# servo_board.net
KiCad netlist of a schematic drawn in EAGLE
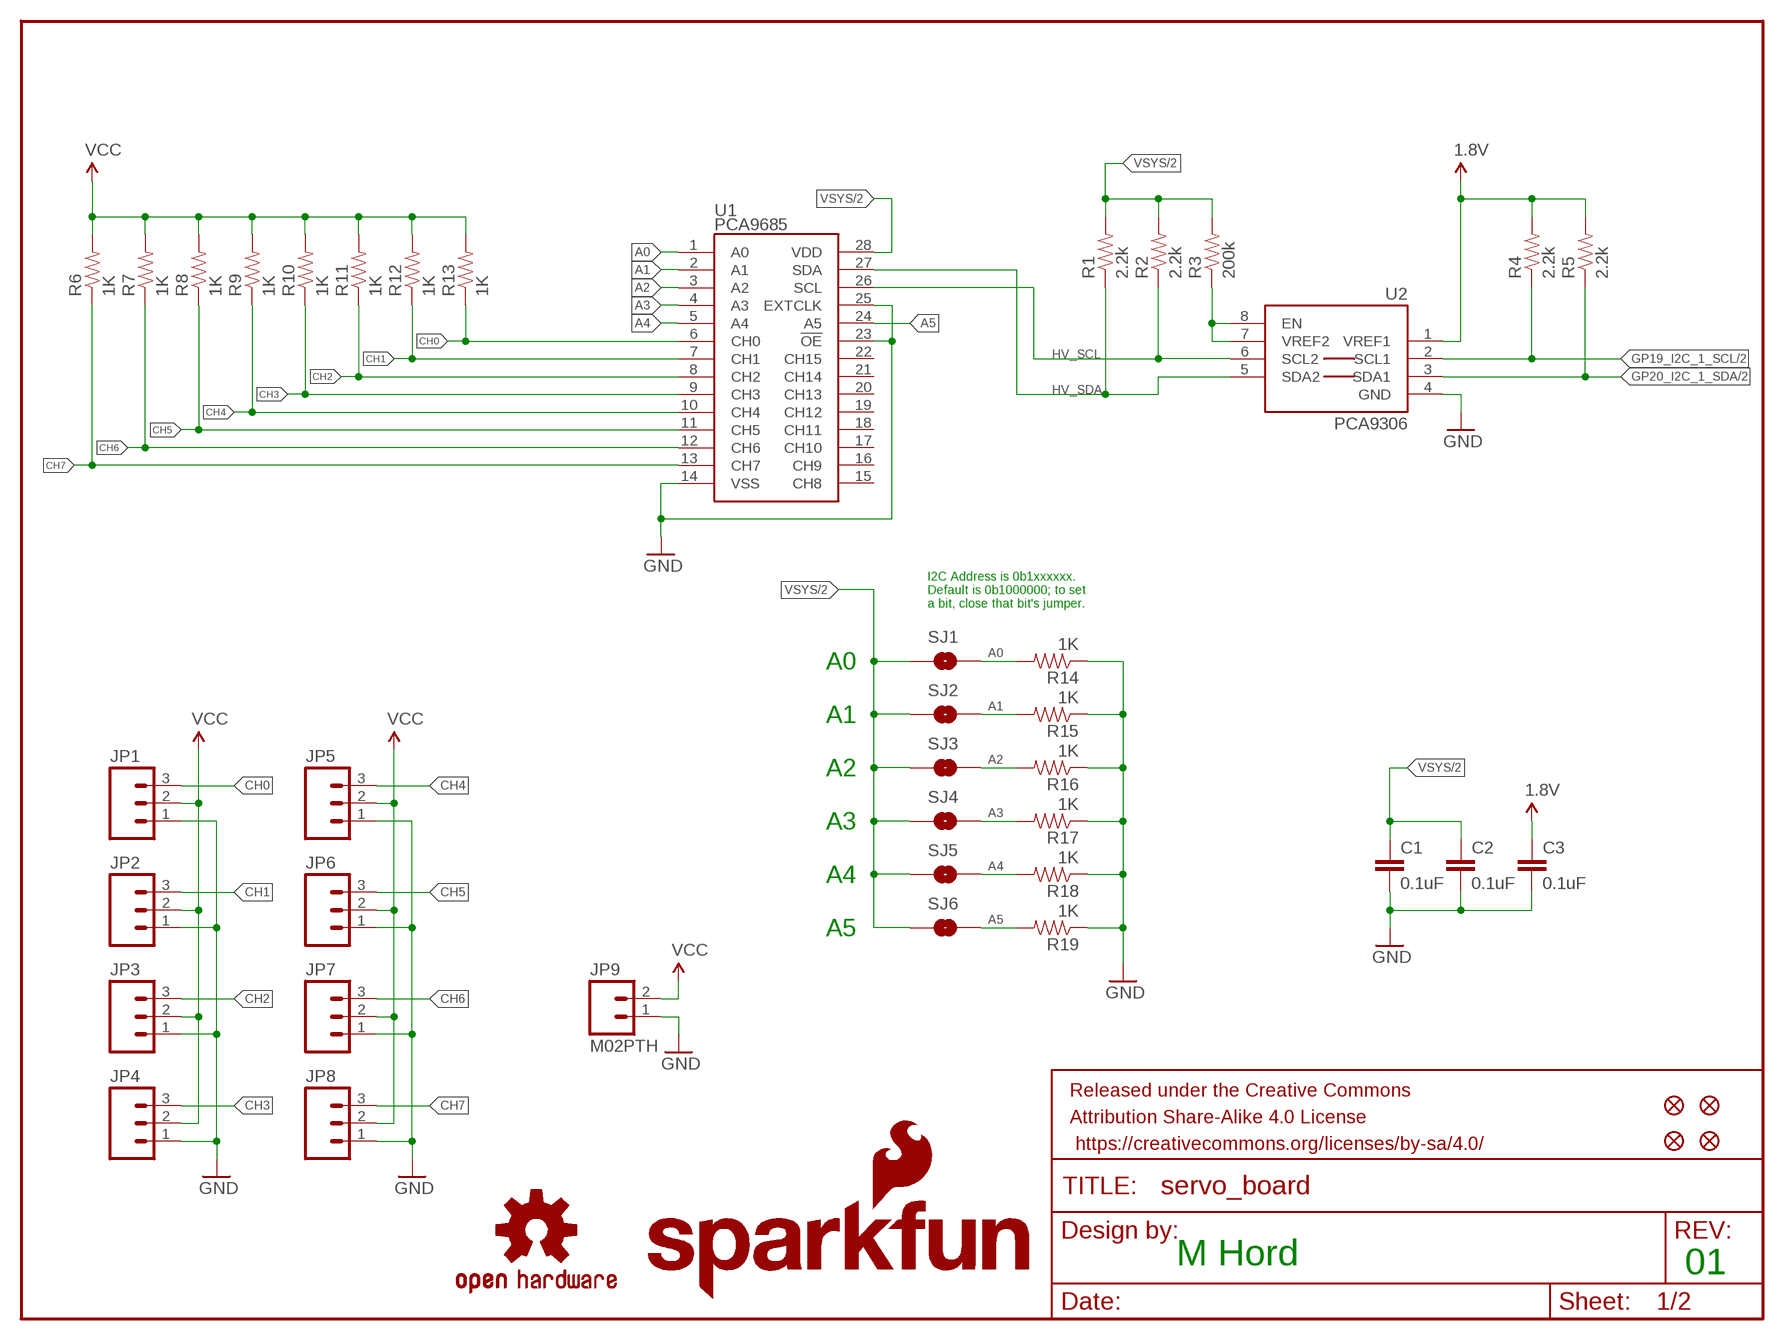
[diagram p0: schematic, sheet 1]
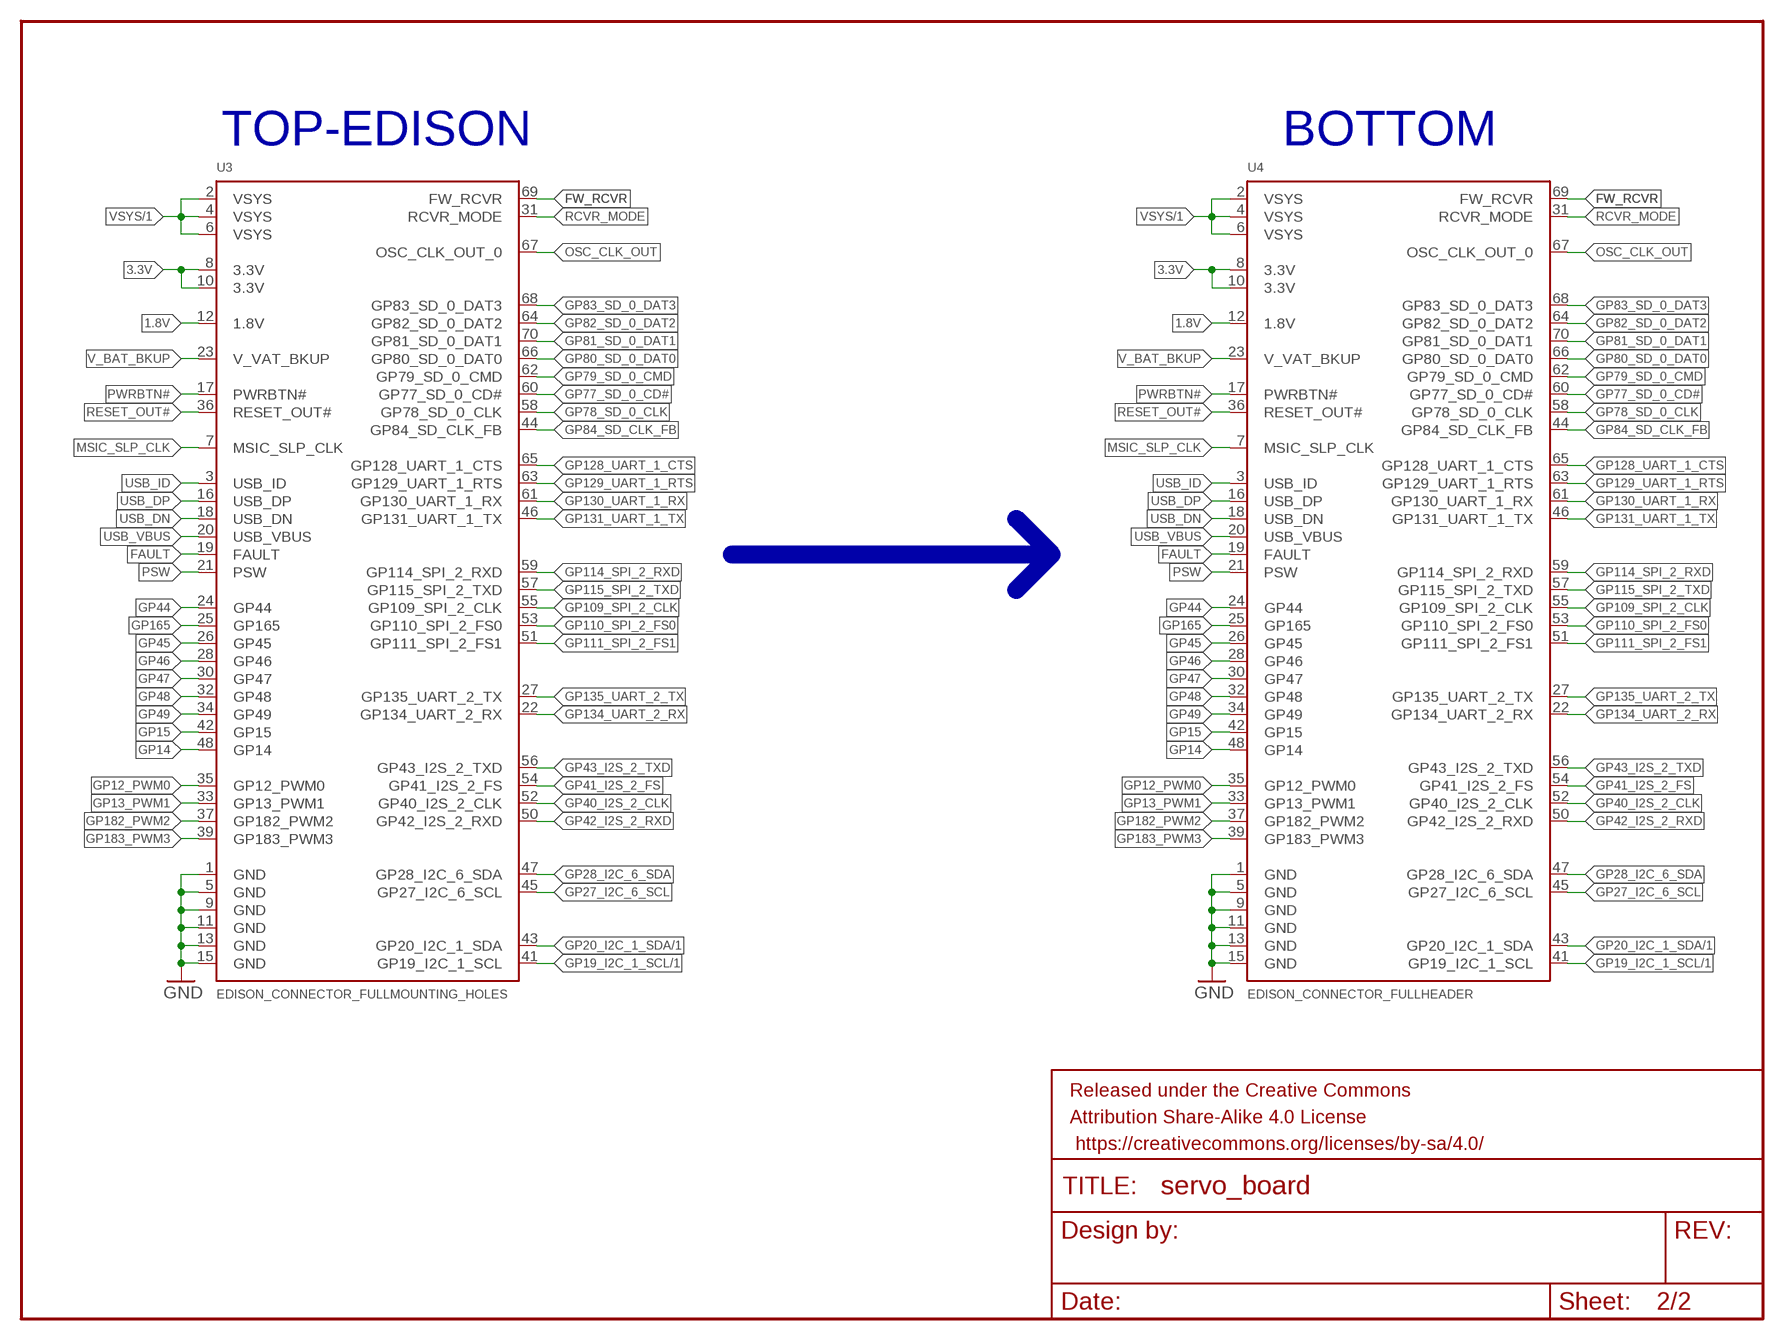
[diagram p1: schematic, sheet 2]

(export (version "E")
  (design (tool "Eeschema 10.0.6"))
  (components
    (comp (ref "FRAME2")
      (value "FRAME-LETTER")
      (footprint "eagle-import:CREATIVE_COMMONS")
      (libsource (lib "eagle-import") (part "FRAME-LETTER"))
    )
    (comp (ref "U3")
      (value "EDISON_CONNECTOR_FULLMOUNTING_HOLES")
      (footprint "eagle-import:EDISON_DAUGHTER")
      (libsource (lib "eagle-import") (part "EDISON_CONNECTOR_FULLMOUNTING_HOLES"))
    )
    (comp (ref "U4")
      (value "EDISON_CONNECTOR_FULLHEADER")
      (footprint "eagle-import:DF40C-70DP-0.4(51)")
      (libsource (lib "eagle-import") (part "EDISON_CONNECTOR_FULLHEADER"))
    )
    (comp (ref "C1")
      (value "0.1uF")
      (footprint "eagle-import:0603-CAP")
      (libsource (lib "eagle-import") (part "0.1UF-25V(+80/-20%)(0603)"))
    )
    (comp (ref "C2")
      (value "0.1uF")
      (footprint "eagle-import:0603-CAP")
      (libsource (lib "eagle-import") (part "0.1UF-25V(+80/-20%)(0603)"))
    )
    (comp (ref "C3")
      (value "0.1uF")
      (footprint "eagle-import:0603-CAP")
      (libsource (lib "eagle-import") (part "0.1UF-25V(+80/-20%)(0603)"))
    )
    (comp (ref "FID1")
      (value "FIDUCIAL1X2")
      (footprint "eagle-import:FIDUCIAL-1X2")
      (libsource (lib "eagle-import") (part "FIDUCIAL1X2"))
    )
    (comp (ref "FID2")
      (value "FIDUCIAL1X2")
      (footprint "eagle-import:FIDUCIAL-1X2")
      (libsource (lib "eagle-import") (part "FIDUCIAL1X2"))
    )
    (comp (ref "FID3")
      (value "FIDUCIAL1X2")
      (footprint "eagle-import:FIDUCIAL-1X2")
      (libsource (lib "eagle-import") (part "FIDUCIAL1X2"))
    )
    (comp (ref "FID4")
      (value "FIDUCIAL1X2")
      (footprint "eagle-import:FIDUCIAL-1X2")
      (libsource (lib "eagle-import") (part "FIDUCIAL1X2"))
    )
    (comp (ref "FRAME1")
      (value "FRAME-LETTER")
      (footprint "eagle-import:CREATIVE_COMMONS")
      (libsource (lib "eagle-import") (part "FRAME-LETTER"))
    )
    (comp (ref "JP1")
      (value "M03PTH")
      (footprint "eagle-import:1X03")
      (libsource (lib "eagle-import") (part "M03PTH"))
    )
    (comp (ref "JP2")
      (value "M03PTH")
      (footprint "eagle-import:1X03")
      (libsource (lib "eagle-import") (part "M03PTH"))
    )
    (comp (ref "JP3")
      (value "M03PTH")
      (footprint "eagle-import:1X03")
      (libsource (lib "eagle-import") (part "M03PTH"))
    )
    (comp (ref "JP4")
      (value "M03PTH")
      (footprint "eagle-import:1X03")
      (libsource (lib "eagle-import") (part "M03PTH"))
    )
    (comp (ref "JP5")
      (value "M03PTH")
      (footprint "eagle-import:1X03")
      (libsource (lib "eagle-import") (part "M03PTH"))
    )
    (comp (ref "JP6")
      (value "M03PTH")
      (footprint "eagle-import:1X03")
      (libsource (lib "eagle-import") (part "M03PTH"))
    )
    (comp (ref "JP7")
      (value "M03PTH")
      (footprint "eagle-import:1X03")
      (libsource (lib "eagle-import") (part "M03PTH"))
    )
    (comp (ref "JP8")
      (value "M03PTH")
      (footprint "eagle-import:1X03")
      (libsource (lib "eagle-import") (part "M03PTH"))
    )
    (comp (ref "JP9")
      (value "M02PTH")
      (footprint "eagle-import:1X02")
      (libsource (lib "eagle-import") (part "M02PTH"))
    )
    (comp (ref "LOGO1")
      (value "SFE_LOGO_NAME_FLAME.1_INCH")
      (footprint "eagle-import:SFE_LOGO_NAME_FLAME_.1")
      (libsource (lib "eagle-import") (part "SFE_LOGO_NAME_FLAME.1_INCH"))
    )
    (comp (ref "LOGO2")
      (value "OSHW-LOGOS")
      (footprint "eagle-import:OSHW-LOGO-S")
      (libsource (lib "eagle-import") (part "OSHW-LOGOS"))
    )
    (comp (ref "LOGO3")
      (value "SFE_LOGO_NAME_FLAME.1_INCH")
      (footprint "eagle-import:SFE_LOGO_NAME_FLAME_.1")
      (libsource (lib "eagle-import") (part "SFE_LOGO_NAME_FLAME.1_INCH"))
    )
    (comp (ref "LOGO4")
      (value "OSHW-LOGOS")
      (footprint "eagle-import:OSHW-LOGO-S")
      (libsource (lib "eagle-import") (part "OSHW-LOGOS"))
    )
    (comp (ref "R1")
      (value "2.2k")
      (footprint "eagle-import:0603-RES")
      (libsource (lib "eagle-import") (part "2.2KOHM1/10W1%(0603)"))
    )
    (comp (ref "R2")
      (value "2.2k")
      (footprint "eagle-import:0603-RES")
      (libsource (lib "eagle-import") (part "2.2KOHM1/10W1%(0603)"))
    )
    (comp (ref "R3")
      (value "200k")
      (footprint "eagle-import:0603-RES")
      (libsource (lib "eagle-import") (part "200KOHM1/10W1%(0603)200K"))
    )
    (comp (ref "R4")
      (value "2.2k")
      (footprint "eagle-import:0603-RES")
      (libsource (lib "eagle-import") (part "2.2KOHM1/10W1%(0603)"))
    )
    (comp (ref "R5")
      (value "2.2k")
      (footprint "eagle-import:0603-RES")
      (libsource (lib "eagle-import") (part "2.2KOHM1/10W1%(0603)"))
    )
    (comp (ref "R6")
      (value "1K")
      (footprint "eagle-import:0603-RES")
      (libsource (lib "eagle-import") (part "1KOHM1/10W1%(0603)"))
    )
    (comp (ref "R7")
      (value "1K")
      (footprint "eagle-import:0603-RES")
      (libsource (lib "eagle-import") (part "1KOHM1/10W1%(0603)"))
    )
    (comp (ref "R8")
      (value "1K")
      (footprint "eagle-import:0603-RES")
      (libsource (lib "eagle-import") (part "1KOHM1/10W1%(0603)"))
    )
    (comp (ref "R9")
      (value "1K")
      (footprint "eagle-import:0603-RES")
      (libsource (lib "eagle-import") (part "1KOHM1/10W1%(0603)"))
    )
    (comp (ref "R10")
      (value "1K")
      (footprint "eagle-import:0603-RES")
      (libsource (lib "eagle-import") (part "1KOHM1/10W1%(0603)"))
    )
    (comp (ref "R11")
      (value "1K")
      (footprint "eagle-import:0603-RES")
      (libsource (lib "eagle-import") (part "1KOHM1/10W1%(0603)"))
    )
    (comp (ref "R12")
      (value "1K")
      (footprint "eagle-import:0603-RES")
      (libsource (lib "eagle-import") (part "1KOHM1/10W1%(0603)"))
    )
    (comp (ref "R13")
      (value "1K")
      (footprint "eagle-import:0603-RES")
      (libsource (lib "eagle-import") (part "1KOHM1/10W1%(0603)"))
    )
    (comp (ref "R14")
      (value "1K")
      (footprint "eagle-import:0603-RES")
      (libsource (lib "eagle-import") (part "1KOHM1/10W1%(0603)"))
    )
    (comp (ref "R15")
      (value "1K")
      (footprint "eagle-import:0603-RES")
      (libsource (lib "eagle-import") (part "1KOHM1/10W1%(0603)"))
    )
    (comp (ref "R16")
      (value "1K")
      (footprint "eagle-import:0603-RES")
      (libsource (lib "eagle-import") (part "1KOHM1/10W1%(0603)"))
    )
    (comp (ref "R17")
      (value "1K")
      (footprint "eagle-import:0603-RES")
      (libsource (lib "eagle-import") (part "1KOHM1/10W1%(0603)"))
    )
    (comp (ref "R18")
      (value "1K")
      (footprint "eagle-import:0603-RES")
      (libsource (lib "eagle-import") (part "1KOHM1/10W1%(0603)"))
    )
    (comp (ref "R19")
      (value "1K")
      (footprint "eagle-import:0603-RES")
      (libsource (lib "eagle-import") (part "1KOHM1/10W1%(0603)"))
    )
    (comp (ref "SJ1")
      (value "JUMPER-PAD-2-NOYES_SILK")
      (footprint "eagle-import:PAD-JUMPER-2-NO_YES_SILK")
      (libsource (lib "eagle-import") (part "JUMPER-PAD-2-NOYES_SILK"))
    )
    (comp (ref "SJ2")
      (value "JUMPER-PAD-2-NOYES_SILK")
      (footprint "eagle-import:PAD-JUMPER-2-NO_YES_SILK")
      (libsource (lib "eagle-import") (part "JUMPER-PAD-2-NOYES_SILK"))
    )
    (comp (ref "SJ3")
      (value "JUMPER-PAD-2-NOYES_SILK")
      (footprint "eagle-import:PAD-JUMPER-2-NO_YES_SILK")
      (libsource (lib "eagle-import") (part "JUMPER-PAD-2-NOYES_SILK"))
    )
    (comp (ref "SJ4")
      (value "JUMPER-PAD-2-NOYES_SILK")
      (footprint "eagle-import:PAD-JUMPER-2-NO_YES_SILK")
      (libsource (lib "eagle-import") (part "JUMPER-PAD-2-NOYES_SILK"))
    )
    (comp (ref "SJ5")
      (value "JUMPER-PAD-2-NOYES_SILK")
      (footprint "eagle-import:PAD-JUMPER-2-NO_YES_SILK")
      (libsource (lib "eagle-import") (part "JUMPER-PAD-2-NOYES_SILK"))
    )
    (comp (ref "SJ6")
      (value "JUMPER-PAD-2-NOYES_SILK")
      (footprint "eagle-import:PAD-JUMPER-2-NO_YES_SILK")
      (libsource (lib "eagle-import") (part "JUMPER-PAD-2-NOYES_SILK"))
    )
    (comp (ref "U1")
      (value "PCA9685")
      (footprint "eagle-import:TSSOP-28_4MM")
      (libsource (lib "eagle-import") (part "PCA9685"))
    )
    (comp (ref "U2")
      (value "PCA9306")
      (footprint "eagle-import:PCA9306DC-1_1")
      (libsource (lib "eagle-import") (part "PCA9306PCA9306DC-1{colon}1"))
    )
  )
  (nets
    (net (code "1") (name "1.8V") (class "Default")
      (node (ref "C3") (pin "1") (pinfunction "1_1") (pintype "passive"))
      (node (ref "R4") (pin "2") (pinfunction "2_2") (pintype "passive"))
      (node (ref "R5") (pin "2") (pinfunction "2_2") (pintype "passive"))
      (node (ref "U2") (pin "1") (pinfunction "VREF1_1") (pintype "bidirectional"))
      (node (ref "U3") (pin "12") (pinfunction "1.8V_12") (pintype "bidirectional"))
      (node (ref "U4") (pin "12") (pinfunction "1.8V_12") (pintype "bidirectional"))
    )
    (net (code "2") (name "3.3V") (class "Default")
      (node (ref "U3") (pin "10") (pinfunction "3.3V_10") (pintype "bidirectional"))
      (node (ref "U3") (pin "8") (pinfunction "3.3V_8") (pintype "bidirectional"))
      (node (ref "U4") (pin "10") (pinfunction "3.3V_10") (pintype "bidirectional"))
      (node (ref "U4") (pin "8") (pinfunction "3.3V_8") (pintype "bidirectional"))
    )
    (net (code "3") (name "A0") (class "Default")
      (node (ref "R14") (pin "2") (pinfunction "2_2") (pintype "passive"))
      (node (ref "SJ1") (pin "2") (pinfunction "2_2") (pintype "passive"))
      (node (ref "U1") (pin "1") (pinfunction "A0_1") (pintype "bidirectional"))
    )
    (net (code "4") (name "A1") (class "Default")
      (node (ref "R15") (pin "2") (pinfunction "2_2") (pintype "passive"))
      (node (ref "SJ2") (pin "2") (pinfunction "2_2") (pintype "passive"))
      (node (ref "U1") (pin "2") (pinfunction "A1_2") (pintype "bidirectional"))
    )
    (net (code "5") (name "A2") (class "Default")
      (node (ref "R16") (pin "2") (pinfunction "2_2") (pintype "passive"))
      (node (ref "SJ3") (pin "2") (pinfunction "2_2") (pintype "passive"))
      (node (ref "U1") (pin "3") (pinfunction "A2_3") (pintype "bidirectional"))
    )
    (net (code "6") (name "A3") (class "Default")
      (node (ref "R17") (pin "2") (pinfunction "2_2") (pintype "passive"))
      (node (ref "SJ4") (pin "2") (pinfunction "2_2") (pintype "passive"))
      (node (ref "U1") (pin "4") (pinfunction "A3_4") (pintype "bidirectional"))
    )
    (net (code "7") (name "A4") (class "Default")
      (node (ref "R18") (pin "2") (pinfunction "2_2") (pintype "passive"))
      (node (ref "SJ5") (pin "2") (pinfunction "2_2") (pintype "passive"))
      (node (ref "U1") (pin "5") (pinfunction "A4_5") (pintype "bidirectional"))
    )
    (net (code "8") (name "A5") (class "Default")
      (node (ref "R19") (pin "2") (pinfunction "2_2") (pintype "passive"))
      (node (ref "SJ6") (pin "2") (pinfunction "2_2") (pintype "passive"))
      (node (ref "U1") (pin "24") (pinfunction "A5_24") (pintype "bidirectional"))
    )
    (net (code "9") (name "CH0") (class "Default")
      (node (ref "JP1") (pin "3") (pinfunction "3_3") (pintype "passive"))
      (node (ref "R13") (pin "1") (pinfunction "1_1") (pintype "passive"))
      (node (ref "U1") (pin "6") (pinfunction "CH0_6") (pintype "bidirectional"))
    )
    (net (code "10") (name "CH1") (class "Default")
      (node (ref "JP2") (pin "3") (pinfunction "3_3") (pintype "passive"))
      (node (ref "R12") (pin "1") (pinfunction "1_1") (pintype "passive"))
      (node (ref "U1") (pin "7") (pinfunction "CH1_7") (pintype "bidirectional"))
    )
    (net (code "11") (name "CH2") (class "Default")
      (node (ref "JP3") (pin "3") (pinfunction "3_3") (pintype "passive"))
      (node (ref "R11") (pin "1") (pinfunction "1_1") (pintype "passive"))
      (node (ref "U1") (pin "8") (pinfunction "CH2_8") (pintype "bidirectional"))
    )
    (net (code "12") (name "CH3") (class "Default")
      (node (ref "JP4") (pin "3") (pinfunction "3_3") (pintype "passive"))
      (node (ref "R10") (pin "1") (pinfunction "1_1") (pintype "passive"))
      (node (ref "U1") (pin "9") (pinfunction "CH3_9") (pintype "bidirectional"))
    )
    (net (code "13") (name "CH4") (class "Default")
      (node (ref "JP5") (pin "3") (pinfunction "3_3") (pintype "passive"))
      (node (ref "R9") (pin "1") (pinfunction "1_1") (pintype "passive"))
      (node (ref "U1") (pin "10") (pinfunction "CH4_10") (pintype "bidirectional"))
    )
    (net (code "14") (name "CH5") (class "Default")
      (node (ref "JP6") (pin "3") (pinfunction "3_3") (pintype "passive"))
      (node (ref "R8") (pin "1") (pinfunction "1_1") (pintype "passive"))
      (node (ref "U1") (pin "11") (pinfunction "CH5_11") (pintype "bidirectional"))
    )
    (net (code "15") (name "CH6") (class "Default")
      (node (ref "JP7") (pin "3") (pinfunction "3_3") (pintype "passive"))
      (node (ref "R7") (pin "1") (pinfunction "1_1") (pintype "passive"))
      (node (ref "U1") (pin "12") (pinfunction "CH6_12") (pintype "bidirectional"))
    )
    (net (code "16") (name "CH7") (class "Default")
      (node (ref "JP8") (pin "3") (pinfunction "3_3") (pintype "passive"))
      (node (ref "R6") (pin "1") (pinfunction "1_1") (pintype "passive"))
      (node (ref "U1") (pin "13") (pinfunction "CH7_13") (pintype "bidirectional"))
    )
    (net (code "17") (name "FAULT") (class "Default")
      (node (ref "U3") (pin "19") (pinfunction "FAULT_19") (pintype "bidirectional"))
      (node (ref "U4") (pin "19") (pinfunction "FAULT_19") (pintype "bidirectional"))
    )
    (net (code "18") (name "FW_RCVR") (class "Default")
      (node (ref "U3") (pin "69") (pinfunction "FW_RCVR_69") (pintype "bidirectional"))
      (node (ref "U4") (pin "69") (pinfunction "FW_RCVR_69") (pintype "bidirectional"))
    )
    (net (code "19") (name "GND") (class "Default")
      (node (ref "C1") (pin "2") (pinfunction "2_2") (pintype "passive"))
      (node (ref "C2") (pin "2") (pinfunction "2_2") (pintype "passive"))
      (node (ref "C3") (pin "2") (pinfunction "2_2") (pintype "passive"))
      (node (ref "JP1") (pin "1") (pinfunction "1_1") (pintype "passive"))
      (node (ref "JP2") (pin "1") (pinfunction "1_1") (pintype "passive"))
      (node (ref "JP3") (pin "1") (pinfunction "1_1") (pintype "passive"))
      (node (ref "JP4") (pin "1") (pinfunction "1_1") (pintype "passive"))
      (node (ref "JP5") (pin "1") (pinfunction "1_1") (pintype "passive"))
      (node (ref "JP6") (pin "1") (pinfunction "1_1") (pintype "passive"))
      (node (ref "JP7") (pin "1") (pinfunction "1_1") (pintype "passive"))
      (node (ref "JP8") (pin "1") (pinfunction "1_1") (pintype "passive"))
      (node (ref "JP9") (pin "1") (pinfunction "1_1") (pintype "passive"))
      (node (ref "R14") (pin "1") (pinfunction "1_1") (pintype "passive"))
      (node (ref "R15") (pin "1") (pinfunction "1_1") (pintype "passive"))
      (node (ref "R16") (pin "1") (pinfunction "1_1") (pintype "passive"))
      (node (ref "R17") (pin "1") (pinfunction "1_1") (pintype "passive"))
      (node (ref "R18") (pin "1") (pinfunction "1_1") (pintype "passive"))
      (node (ref "R19") (pin "1") (pinfunction "1_1") (pintype "passive"))
      (node (ref "U1") (pin "14") (pinfunction "VSS_14") (pintype "bidirectional"))
      (node (ref "U1") (pin "23") (pinfunction "~{OE}_23") (pintype "bidirectional"))
      (node (ref "U1") (pin "25") (pinfunction "EXTCLK_25") (pintype "bidirectional"))
      (node (ref "U2") (pin "4") (pinfunction "GND_4") (pintype "bidirectional"))
      (node (ref "U3") (pin "1") (pinfunction "GND_1") (pintype "bidirectional"))
      (node (ref "U3") (pin "11") (pinfunction "GND_11") (pintype "bidirectional"))
      (node (ref "U3") (pin "13") (pinfunction "GND_13") (pintype "bidirectional"))
      (node (ref "U3") (pin "15") (pinfunction "GND_15") (pintype "bidirectional"))
      (node (ref "U3") (pin "5") (pinfunction "GND_5") (pintype "bidirectional"))
      (node (ref "U3") (pin "9") (pinfunction "GND_9") (pintype "bidirectional"))
      (node (ref "U4") (pin "1") (pinfunction "GND_1") (pintype "bidirectional"))
      (node (ref "U4") (pin "11") (pinfunction "GND_11") (pintype "bidirectional"))
      (node (ref "U4") (pin "13") (pinfunction "GND_13") (pintype "bidirectional"))
      (node (ref "U4") (pin "15") (pinfunction "GND_15") (pintype "bidirectional"))
      (node (ref "U4") (pin "5") (pinfunction "GND_5") (pintype "bidirectional"))
      (node (ref "U4") (pin "9") (pinfunction "GND_9") (pintype "bidirectional"))
    )
    (net (code "20") (name "GP12_PWM0") (class "Default")
      (node (ref "U3") (pin "35") (pinfunction "GP12_PWM0_35") (pintype "bidirectional"))
      (node (ref "U4") (pin "35") (pinfunction "GP12_PWM0_35") (pintype "bidirectional"))
    )
    (net (code "21") (name "GP13_PWM1") (class "Default")
      (node (ref "U3") (pin "33") (pinfunction "GP13_PWM1_33") (pintype "bidirectional"))
      (node (ref "U4") (pin "33") (pinfunction "GP13_PWM1_33") (pintype "bidirectional"))
    )
    (net (code "22") (name "GP14") (class "Default")
      (node (ref "U3") (pin "48") (pinfunction "GP14_48") (pintype "bidirectional"))
      (node (ref "U4") (pin "48") (pinfunction "GP14_48") (pintype "bidirectional"))
    )
    (net (code "23") (name "GP15") (class "Default")
      (node (ref "U3") (pin "42") (pinfunction "GP15_42") (pintype "bidirectional"))
      (node (ref "U4") (pin "42") (pinfunction "GP15_42") (pintype "bidirectional"))
    )
    (net (code "24") (name "GP19_I2C_1_SCL") (class "Default")
      (node (ref "R4") (pin "1") (pinfunction "1_1") (pintype "passive"))
      (node (ref "U2") (pin "2") (pinfunction "SCL1_2") (pintype "bidirectional"))
      (node (ref "U3") (pin "41") (pinfunction "GP19_I2C_1_SCL_41") (pintype "bidirectional"))
      (node (ref "U4") (pin "41") (pinfunction "GP19_I2C_1_SCL_41") (pintype "bidirectional"))
    )
    (net (code "25") (name "GP20_I2C_1_SDA") (class "Default")
      (node (ref "R5") (pin "1") (pinfunction "1_1") (pintype "passive"))
      (node (ref "U2") (pin "3") (pinfunction "SDA1_3") (pintype "bidirectional"))
      (node (ref "U3") (pin "43") (pinfunction "GP20_I2C_1_SDA_43") (pintype "bidirectional"))
      (node (ref "U4") (pin "43") (pinfunction "GP20_I2C_1_SDA_43") (pintype "bidirectional"))
    )
    (net (code "26") (name "GP27_I2C_6_SCL") (class "Default")
      (node (ref "U3") (pin "45") (pinfunction "GP27_I2C_6_SCL_45") (pintype "bidirectional"))
      (node (ref "U4") (pin "45") (pinfunction "GP27_I2C_6_SCL_45") (pintype "bidirectional"))
    )
    (net (code "27") (name "GP28_I2C_6_SDA") (class "Default")
      (node (ref "U3") (pin "47") (pinfunction "GP28_I2C_6_SDA_47") (pintype "bidirectional"))
      (node (ref "U4") (pin "47") (pinfunction "GP28_I2C_6_SDA_47") (pintype "bidirectional"))
    )
    (net (code "28") (name "GP40_I2S_2_CLK") (class "Default")
      (node (ref "U3") (pin "52") (pinfunction "GP40_I2S_2_CLK_52") (pintype "bidirectional"))
      (node (ref "U4") (pin "52") (pinfunction "GP40_I2S_2_CLK_52") (pintype "bidirectional"))
    )
    (net (code "29") (name "GP41_I2S_2_FS") (class "Default")
      (node (ref "U3") (pin "54") (pinfunction "GP41_I2S_2_FS_54") (pintype "bidirectional"))
      (node (ref "U4") (pin "54") (pinfunction "GP41_I2S_2_FS_54") (pintype "bidirectional"))
    )
    (net (code "30") (name "GP42_I2S_2_RXD") (class "Default")
      (node (ref "U3") (pin "50") (pinfunction "GP42_I2S_2_RXD_50") (pintype "bidirectional"))
      (node (ref "U4") (pin "50") (pinfunction "GP42_I2S_2_RXD_50") (pintype "bidirectional"))
    )
    (net (code "31") (name "GP43_I2S_2_TXD") (class "Default")
      (node (ref "U3") (pin "56") (pinfunction "GP43_I2S_2_TXD_56") (pintype "bidirectional"))
      (node (ref "U4") (pin "56") (pinfunction "GP43_I2S_2_TXD_56") (pintype "bidirectional"))
    )
    (net (code "32") (name "GP44") (class "Default")
      (node (ref "U3") (pin "24") (pinfunction "GP44_24") (pintype "bidirectional"))
      (node (ref "U4") (pin "24") (pinfunction "GP44_24") (pintype "bidirectional"))
    )
    (net (code "33") (name "GP45") (class "Default")
      (node (ref "U3") (pin "26") (pinfunction "GP45_26") (pintype "bidirectional"))
      (node (ref "U4") (pin "26") (pinfunction "GP45_26") (pintype "bidirectional"))
    )
    (net (code "34") (name "GP46") (class "Default")
      (node (ref "U3") (pin "28") (pinfunction "GP46_28") (pintype "bidirectional"))
      (node (ref "U4") (pin "28") (pinfunction "GP46_28") (pintype "bidirectional"))
    )
    (net (code "35") (name "GP47") (class "Default")
      (node (ref "U3") (pin "30") (pinfunction "GP47_30") (pintype "bidirectional"))
      (node (ref "U4") (pin "30") (pinfunction "GP47_30") (pintype "bidirectional"))
    )
    (net (code "36") (name "GP48") (class "Default")
      (node (ref "U3") (pin "32") (pinfunction "GP48_32") (pintype "bidirectional"))
      (node (ref "U4") (pin "32") (pinfunction "GP48_32") (pintype "bidirectional"))
    )
    (net (code "37") (name "GP49") (class "Default")
      (node (ref "U3") (pin "34") (pinfunction "GP49_34") (pintype "bidirectional"))
      (node (ref "U4") (pin "34") (pinfunction "GP49_34") (pintype "bidirectional"))
    )
    (net (code "38") (name "GP77_SD_0_CD#") (class "Default")
      (node (ref "U3") (pin "60") (pinfunction "GP77_SD_0_CD#_60") (pintype "bidirectional"))
      (node (ref "U4") (pin "60") (pinfunction "GP77_SD_0_CD#_60") (pintype "bidirectional"))
    )
    (net (code "39") (name "GP78_SD_0_CLK") (class "Default")
      (node (ref "U3") (pin "58") (pinfunction "GP78_SD_0_CLK_58") (pintype "bidirectional"))
      (node (ref "U4") (pin "58") (pinfunction "GP78_SD_0_CLK_58") (pintype "bidirectional"))
    )
    (net (code "40") (name "GP79_SD_0_CMD") (class "Default")
      (node (ref "U3") (pin "62") (pinfunction "GP79_SD_0_CMD_62") (pintype "bidirectional"))
      (node (ref "U4") (pin "62") (pinfunction "GP79_SD_0_CMD_62") (pintype "bidirectional"))
    )
    (net (code "41") (name "GP80_SD_0_DAT0") (class "Default")
      (node (ref "U3") (pin "66") (pinfunction "GP80_SD_0_DAT0_66") (pintype "bidirectional"))
      (node (ref "U4") (pin "66") (pinfunction "GP80_SD_0_DAT0_66") (pintype "bidirectional"))
    )
    (net (code "42") (name "GP81_SD_0_DAT1") (class "Default")
      (node (ref "U3") (pin "70") (pinfunction "GP81_SD_0_DAT1_70") (pintype "bidirectional"))
      (node (ref "U4") (pin "70") (pinfunction "GP81_SD_0_DAT1_70") (pintype "bidirectional"))
    )
    (net (code "43") (name "GP82_SD_0_DAT2") (class "Default")
      (node (ref "U3") (pin "64") (pinfunction "GP82_SD_0_DAT2_64") (pintype "bidirectional"))
      (node (ref "U4") (pin "64") (pinfunction "GP82_SD_0_DAT2_64") (pintype "bidirectional"))
    )
    (net (code "44") (name "GP83_SD_0_DAT3") (class "Default")
      (node (ref "U3") (pin "68") (pinfunction "GP83_SD_0_DAT3_68") (pintype "bidirectional"))
      (node (ref "U4") (pin "68") (pinfunction "GP83_SD_0_DAT3_68") (pintype "bidirectional"))
    )
    (net (code "45") (name "GP84_SD_CLK_FB") (class "Default")
      (node (ref "U3") (pin "44") (pinfunction "GP84_SD_CLK_FB_44") (pintype "bidirectional"))
      (node (ref "U4") (pin "44") (pinfunction "GP84_SD_CLK_FB_44") (pintype "bidirectional"))
    )
    (net (code "46") (name "GP109_SPI_2_CLK") (class "Default")
      (node (ref "U3") (pin "55") (pinfunction "GP109_SPI_2_CLK_55") (pintype "bidirectional"))
      (node (ref "U4") (pin "55") (pinfunction "GP109_SPI_2_CLK_55") (pintype "bidirectional"))
    )
    (net (code "47") (name "GP110_SPI_2_FS0") (class "Default")
      (node (ref "U3") (pin "53") (pinfunction "GP110_SPI_2_FS0_53") (pintype "bidirectional"))
      (node (ref "U4") (pin "53") (pinfunction "GP110_SPI_2_FS0_53") (pintype "bidirectional"))
    )
    (net (code "48") (name "GP111_SPI_2_FS1") (class "Default")
      (node (ref "U3") (pin "51") (pinfunction "GP111_SPI_2_FS1_51") (pintype "bidirectional"))
      (node (ref "U4") (pin "51") (pinfunction "GP111_SPI_2_FS1_51") (pintype "bidirectional"))
    )
    (net (code "49") (name "GP114_SPI_2_RXD") (class "Default")
      (node (ref "U3") (pin "59") (pinfunction "GP114_SPI_2_RXD_59") (pintype "bidirectional"))
      (node (ref "U4") (pin "59") (pinfunction "GP114_SPI_2_RXD_59") (pintype "bidirectional"))
    )
    (net (code "50") (name "GP115_SPI_2_TXD") (class "Default")
      (node (ref "U3") (pin "57") (pinfunction "GP115_SPI_2_TXD_57") (pintype "bidirectional"))
      (node (ref "U4") (pin "57") (pinfunction "GP115_SPI_2_TXD_57") (pintype "bidirectional"))
    )
    (net (code "51") (name "GP128_UART_1_CTS") (class "Default")
      (node (ref "U3") (pin "65") (pinfunction "GP128_UART_1_CTS_65") (pintype "bidirectional"))
      (node (ref "U4") (pin "65") (pinfunction "GP128_UART_1_CTS_65") (pintype "bidirectional"))
    )
    (net (code "52") (name "GP129_UART_1_RTS") (class "Default")
      (node (ref "U3") (pin "63") (pinfunction "GP129_UART_1_RTS_63") (pintype "bidirectional"))
      (node (ref "U4") (pin "63") (pinfunction "GP129_UART_1_RTS_63") (pintype "bidirectional"))
    )
    (net (code "53") (name "GP130_UART_1_RX") (class "Default")
      (node (ref "U3") (pin "61") (pinfunction "GP130_UART_1_RX_61") (pintype "bidirectional"))
      (node (ref "U4") (pin "61") (pinfunction "GP130_UART_1_RX_61") (pintype "bidirectional"))
    )
    (net (code "54") (name "GP131_UART_1_TX") (class "Default")
      (node (ref "U3") (pin "46") (pinfunction "GP131_UART_1_TX_46") (pintype "bidirectional"))
      (node (ref "U4") (pin "46") (pinfunction "GP131_UART_1_TX_46") (pintype "bidirectional"))
    )
    (net (code "55") (name "GP134_UART_2_RX") (class "Default")
      (node (ref "U3") (pin "22") (pinfunction "GP134_UART_2_RX_22") (pintype "bidirectional"))
      (node (ref "U4") (pin "22") (pinfunction "GP134_UART_2_RX_22") (pintype "bidirectional"))
    )
    (net (code "56") (name "GP135_UART_2_TX") (class "Default")
      (node (ref "U3") (pin "27") (pinfunction "GP135_UART_2_TX_27") (pintype "bidirectional"))
      (node (ref "U4") (pin "27") (pinfunction "GP135_UART_2_TX_27") (pintype "bidirectional"))
    )
    (net (code "57") (name "GP165") (class "Default")
      (node (ref "U3") (pin "25") (pinfunction "GP165_25") (pintype "bidirectional"))
      (node (ref "U4") (pin "25") (pinfunction "GP165_25") (pintype "bidirectional"))
    )
    (net (code "58") (name "GP182_PWM2") (class "Default")
      (node (ref "U3") (pin "37") (pinfunction "GP182_PWM2_37") (pintype "bidirectional"))
      (node (ref "U4") (pin "37") (pinfunction "GP182_PWM2_37") (pintype "bidirectional"))
    )
    (net (code "59") (name "GP183_PWM3") (class "Default")
      (node (ref "U3") (pin "39") (pinfunction "GP183_PWM3_39") (pintype "bidirectional"))
      (node (ref "U4") (pin "39") (pinfunction "GP183_PWM3_39") (pintype "bidirectional"))
    )
    (net (code "60") (name "HV_SCL") (class "Default")
      (node (ref "R2") (pin "1") (pinfunction "1_1") (pintype "passive"))
      (node (ref "U1") (pin "26") (pinfunction "SCL_26") (pintype "bidirectional"))
      (node (ref "U2") (pin "6") (pinfunction "SCL2_6") (pintype "bidirectional"))
    )
    (net (code "61") (name "HV_SDA") (class "Default")
      (node (ref "R1") (pin "1") (pinfunction "1_1") (pintype "passive"))
      (node (ref "U1") (pin "27") (pinfunction "SDA_27") (pintype "bidirectional"))
      (node (ref "U2") (pin "5") (pinfunction "SDA2_5") (pintype "bidirectional"))
    )
    (net (code "62") (name "MSIC_SLP_CLK") (class "Default")
      (node (ref "U3") (pin "7") (pinfunction "MSIC_SLP_CLK_7") (pintype "bidirectional"))
      (node (ref "U4") (pin "7") (pinfunction "MSIC_SLP_CLK_7") (pintype "bidirectional"))
    )
    (net (code "63") (name "Net-(U2-EN)") (class "Default")
      (node (ref "R3") (pin "1") (pinfunction "1_1") (pintype "passive"))
      (node (ref "U2") (pin "7") (pinfunction "VREF2_7") (pintype "bidirectional"))
      (node (ref "U2") (pin "8") (pinfunction "EN_8") (pintype "bidirectional"))
    )
    (net (code "64") (name "OSC_CLK_OUT") (class "Default")
      (node (ref "U3") (pin "67") (pinfunction "OSC_CLK_OUT_0_67") (pintype "bidirectional"))
      (node (ref "U4") (pin "67") (pinfunction "OSC_CLK_OUT_0_67") (pintype "bidirectional"))
    )
    (net (code "65") (name "PSW") (class "Default")
      (node (ref "U3") (pin "21") (pinfunction "PSW_21") (pintype "bidirectional"))
      (node (ref "U4") (pin "21") (pinfunction "PSW_21") (pintype "bidirectional"))
    )
    (net (code "66") (name "PWRBTN#") (class "Default")
      (node (ref "U3") (pin "17") (pinfunction "PWRBTN#_17") (pintype "bidirectional"))
      (node (ref "U4") (pin "17") (pinfunction "PWRBTN#_17") (pintype "bidirectional"))
    )
    (net (code "67") (name "RCVR_MODE") (class "Default")
      (node (ref "U3") (pin "31") (pinfunction "RCVR_MODE_31") (pintype "bidirectional"))
      (node (ref "U4") (pin "31") (pinfunction "RCVR_MODE_31") (pintype "bidirectional"))
    )
    (net (code "68") (name "RESET_OUT#") (class "Default")
      (node (ref "U3") (pin "36") (pinfunction "RESET_OUT#_36") (pintype "bidirectional"))
      (node (ref "U4") (pin "36") (pinfunction "RESET_OUT#_36") (pintype "bidirectional"))
    )
    (net (code "69") (name "USB_DN") (class "Default")
      (node (ref "U3") (pin "18") (pinfunction "USB_DN_18") (pintype "bidirectional"))
      (node (ref "U4") (pin "18") (pinfunction "USB_DN_18") (pintype "bidirectional"))
    )
    (net (code "70") (name "USB_DP") (class "Default")
      (node (ref "U3") (pin "16") (pinfunction "USB_DP_16") (pintype "bidirectional"))
      (node (ref "U4") (pin "16") (pinfunction "USB_DP_16") (pintype "bidirectional"))
    )
    (net (code "71") (name "USB_ID") (class "Default")
      (node (ref "U3") (pin "3") (pinfunction "USB_ID_3") (pintype "bidirectional"))
      (node (ref "U4") (pin "3") (pinfunction "USB_ID_3") (pintype "bidirectional"))
    )
    (net (code "72") (name "USB_VBUS") (class "Default")
      (node (ref "U3") (pin "20") (pinfunction "USB_VBUS_20") (pintype "bidirectional"))
      (node (ref "U4") (pin "20") (pinfunction "USB_VBUS_20") (pintype "bidirectional"))
    )
    (net (code "73") (name "VCC") (class "Default")
      (node (ref "JP1") (pin "2") (pinfunction "2_2") (pintype "passive"))
      (node (ref "JP2") (pin "2") (pinfunction "2_2") (pintype "passive"))
      (node (ref "JP3") (pin "2") (pinfunction "2_2") (pintype "passive"))
      (node (ref "JP4") (pin "2") (pinfunction "2_2") (pintype "passive"))
      (node (ref "JP5") (pin "2") (pinfunction "2_2") (pintype "passive"))
      (node (ref "JP6") (pin "2") (pinfunction "2_2") (pintype "passive"))
      (node (ref "JP7") (pin "2") (pinfunction "2_2") (pintype "passive"))
      (node (ref "JP8") (pin "2") (pinfunction "2_2") (pintype "passive"))
      (node (ref "JP9") (pin "2") (pinfunction "2_2") (pintype "passive"))
      (node (ref "R10") (pin "2") (pinfunction "2_2") (pintype "passive"))
      (node (ref "R11") (pin "2") (pinfunction "2_2") (pintype "passive"))
      (node (ref "R12") (pin "2") (pinfunction "2_2") (pintype "passive"))
      (node (ref "R13") (pin "2") (pinfunction "2_2") (pintype "passive"))
      (node (ref "R6") (pin "2") (pinfunction "2_2") (pintype "passive"))
      (node (ref "R7") (pin "2") (pinfunction "2_2") (pintype "passive"))
      (node (ref "R8") (pin "2") (pinfunction "2_2") (pintype "passive"))
      (node (ref "R9") (pin "2") (pinfunction "2_2") (pintype "passive"))
    )
    (net (code "74") (name "VSYS") (class "Default")
      (node (ref "C1") (pin "1") (pinfunction "1_1") (pintype "passive"))
      (node (ref "C2") (pin "1") (pinfunction "1_1") (pintype "passive"))
      (node (ref "R1") (pin "2") (pinfunction "2_2") (pintype "passive"))
      (node (ref "R2") (pin "2") (pinfunction "2_2") (pintype "passive"))
      (node (ref "R3") (pin "2") (pinfunction "2_2") (pintype "passive"))
      (node (ref "SJ1") (pin "1") (pinfunction "1_1") (pintype "passive"))
      (node (ref "SJ2") (pin "1") (pinfunction "1_1") (pintype "passive"))
      (node (ref "SJ3") (pin "1") (pinfunction "1_1") (pintype "passive"))
      (node (ref "SJ4") (pin "1") (pinfunction "1_1") (pintype "passive"))
      (node (ref "SJ5") (pin "1") (pinfunction "1_1") (pintype "passive"))
      (node (ref "SJ6") (pin "1") (pinfunction "1_1") (pintype "passive"))
      (node (ref "U1") (pin "28") (pinfunction "VDD_28") (pintype "bidirectional"))
      (node (ref "U3") (pin "2") (pinfunction "VSYS_2") (pintype "bidirectional"))
      (node (ref "U3") (pin "4") (pinfunction "VSYS_4") (pintype "bidirectional"))
      (node (ref "U3") (pin "6") (pinfunction "VSYS_6") (pintype "bidirectional"))
      (node (ref "U4") (pin "2") (pinfunction "VSYS_2") (pintype "bidirectional"))
      (node (ref "U4") (pin "4") (pinfunction "VSYS_4") (pintype "bidirectional"))
      (node (ref "U4") (pin "6") (pinfunction "VSYS_6") (pintype "bidirectional"))
    )
    (net (code "75") (name "V_BAT_BKUP") (class "Default")
      (node (ref "U3") (pin "23") (pinfunction "V_VAT_BKUP_23") (pintype "bidirectional"))
      (node (ref "U4") (pin "23") (pinfunction "V_VAT_BKUP_23") (pintype "bidirectional"))
    )
    (net (code "76") (name "unconnected-(U1-CH8-Pad15)") (class "Default")
      (node (ref "U1") (pin "15") (pinfunction "CH8_15") (pintype "bidirectional"))
    )
    (net (code "77") (name "unconnected-(U1-CH9-Pad16)") (class "Default")
      (node (ref "U1") (pin "16") (pinfunction "CH9_16") (pintype "bidirectional"))
    )
    (net (code "78") (name "unconnected-(U1-CH10-Pad17)") (class "Default")
      (node (ref "U1") (pin "17") (pinfunction "CH10_17") (pintype "bidirectional"))
    )
    (net (code "79") (name "unconnected-(U1-CH11-Pad18)") (class "Default")
      (node (ref "U1") (pin "18") (pinfunction "CH11_18") (pintype "bidirectional"))
    )
    (net (code "80") (name "unconnected-(U1-CH12-Pad19)") (class "Default")
      (node (ref "U1") (pin "19") (pinfunction "CH12_19") (pintype "bidirectional"))
    )
    (net (code "81") (name "unconnected-(U1-CH13-Pad20)") (class "Default")
      (node (ref "U1") (pin "20") (pinfunction "CH13_20") (pintype "bidirectional"))
    )
    (net (code "82") (name "unconnected-(U1-CH14-Pad21)") (class "Default")
      (node (ref "U1") (pin "21") (pinfunction "CH14_21") (pintype "bidirectional"))
    )
    (net (code "83") (name "unconnected-(U1-CH15-Pad22)") (class "Default")
      (node (ref "U1") (pin "22") (pinfunction "CH15_22") (pintype "bidirectional"))
    )
  )
)
